# Connections.net
KiCad netlist of a schematic drawn in Altium Designer
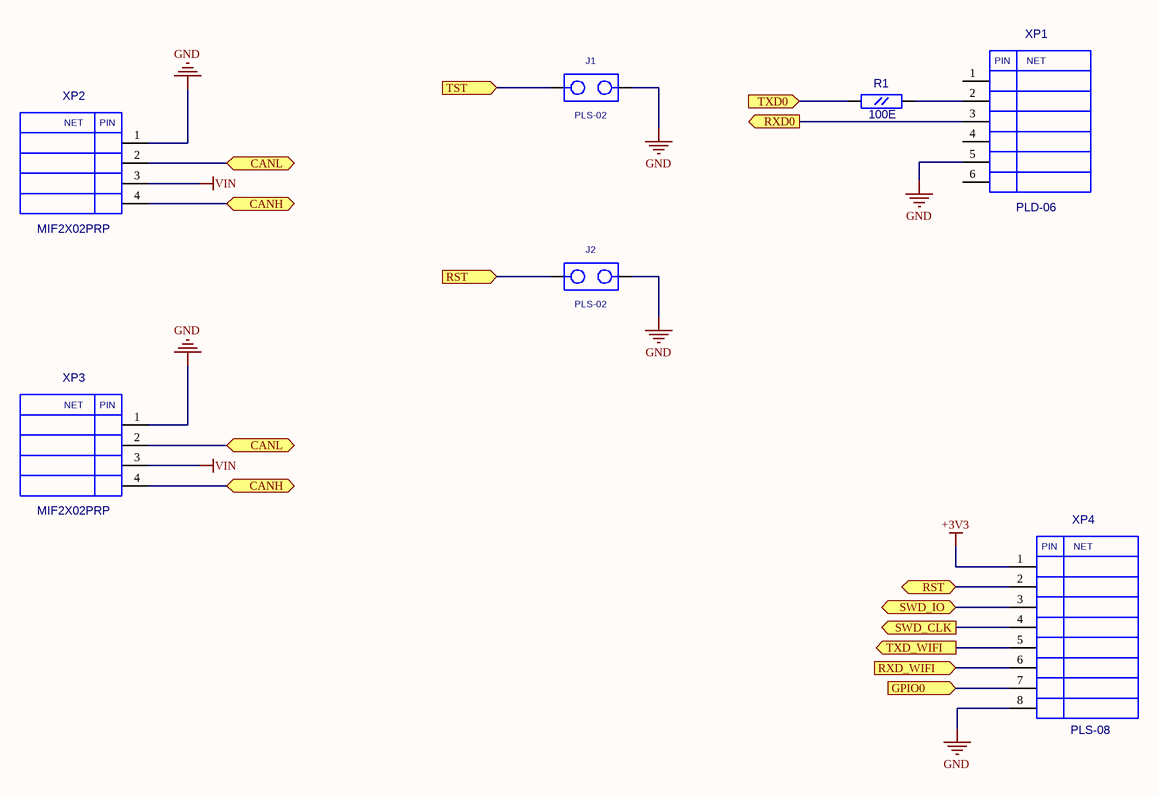
[diagram p0: Connections.SchDoc]

(export (version "E")
  (design (tool "Eeschema 10.0.6"))
  (components
    (comp (ref "J1") (value "PLS-02") (footprint "PLS-02") (libsource (lib "gprs_modem_2") (part "PLS-02")))
    (comp (ref "J2") (value "PLS-02") (footprint "PLS-02") (libsource (lib "gprs_modem_2") (part "PLS-02")))
    (comp (ref "R1")
      (value "100E")
      (footprint "RC0603")
      (description "RC0603")
      (libsource (lib "gprs_modem_2") (part "RC0603"))
    )
    (comp (ref "XP1")
      (value "PLD-06")
      (footprint "PIN6")
      (description "PLD06")
      (libsource (lib "gprs_modem_2") (part "PLD-06"))
    )
    (comp (ref "XP2")
      (value "MIF2X02PRP")
      (footprint "MIF2X02PRP")
      (libsource (lib "gprs_modem_2") (part "MIF2X02PRP"))
    )
    (comp (ref "XP3")
      (value "MIF2X02PRP")
      (footprint "MIF2X02PRP")
      (libsource (lib "gprs_modem_2") (part "MIF2X02PRP"))
    )
    (comp (ref "XP4") (value "PLS-08") (footprint "PLS-08") (libsource (lib "gprs_modem_2") (part "PLS-08")))
  )
  (nets
    (net (code "1") (name "+3V3") (class "Default")
      (node (ref "XP4") (pin "1") (pinfunction "1_1") (pintype "passive"))
    )
    (net (code "2") (name "/CANH") (class "Default")
      (node (ref "XP2") (pin "4") (pinfunction "4_4") (pintype "passive"))
      (node (ref "XP3") (pin "4") (pinfunction "4_4") (pintype "passive"))
    )
    (net (code "3") (name "/CANL") (class "Default")
      (node (ref "XP2") (pin "2") (pinfunction "2_2") (pintype "passive"))
      (node (ref "XP3") (pin "2") (pinfunction "2_2") (pintype "passive"))
    )
    (net (code "4") (name "/GPIO0") (class "Default")
      (node (ref "XP4") (pin "7") (pinfunction "7_7") (pintype "passive"))
    )
    (net (code "5") (name "/RST") (class "Default")
      (node (ref "J2") (pin "1") (pintype "passive"))
      (node (ref "XP4") (pin "2") (pinfunction "2_2") (pintype "passive"))
    )
    (net (code "6") (name "/RXD0") (class "Default")
      (node (ref "XP1") (pin "3") (pinfunction "3_3") (pintype "passive"))
    )
    (net (code "7") (name "/RXD_WIFI") (class "Default")
      (node (ref "XP4") (pin "6") (pinfunction "6_6") (pintype "passive"))
    )
    (net (code "8") (name "/SWD_CLK") (class "Default")
      (node (ref "XP4") (pin "4") (pinfunction "4_4") (pintype "passive"))
    )
    (net (code "9") (name "/SWD_IO") (class "Default")
      (node (ref "XP4") (pin "3") (pinfunction "3_3") (pintype "passive"))
    )
    (net (code "10") (name "/TST") (class "Default") (node (ref "J1") (pin "1") (pintype "passive")))
    (net (code "11") (name "/TXD0") (class "Default")
      (node (ref "R1") (pin "1") (pinfunction "A_1") (pintype "passive"))
    )
    (net (code "12") (name "/TXD_WIFI") (class "Default")
      (node (ref "XP4") (pin "5") (pinfunction "5_5") (pintype "passive"))
    )
    (net (code "13") (name "GND") (class "Default")
      (node (ref "J1") (pin "2") (pintype "passive"))
      (node (ref "J2") (pin "2") (pintype "passive"))
      (node (ref "XP1") (pin "5") (pinfunction "5_5") (pintype "passive"))
      (node (ref "XP2") (pin "1") (pinfunction "1_1") (pintype "passive"))
      (node (ref "XP3") (pin "1") (pinfunction "1_1") (pintype "passive"))
      (node (ref "XP4") (pin "8") (pinfunction "8_8") (pintype "passive"))
    )
    (net (code "14") (name "Net-(R1-B)") (class "Default")
      (node (ref "R1") (pin "2") (pinfunction "B_2") (pintype "passive"))
      (node (ref "XP1") (pin "2") (pinfunction "2_2") (pintype "passive"))
    )
    (net (code "15") (name "VIN") (class "Default")
      (node (ref "XP2") (pin "3") (pinfunction "3_3") (pintype "passive"))
      (node (ref "XP3") (pin "3") (pinfunction "3_3") (pintype "passive"))
    )
    (net (code "16") (name "unconnected-(XP1-Pad1)") (class "Default")
      (node (ref "XP1") (pin "1") (pinfunction "1_1") (pintype "passive"))
    )
    (net (code "17") (name "unconnected-(XP1-Pad4)") (class "Default")
      (node (ref "XP1") (pin "4") (pinfunction "4_4") (pintype "passive"))
    )
    (net (code "18") (name "unconnected-(XP1-Pad6)") (class "Default")
      (node (ref "XP1") (pin "6") (pinfunction "6_6") (pintype "passive"))
    )
  )
)
